# CPCISerial_connector.net
KiCad netlist of a schematic drawn in Altium Designer
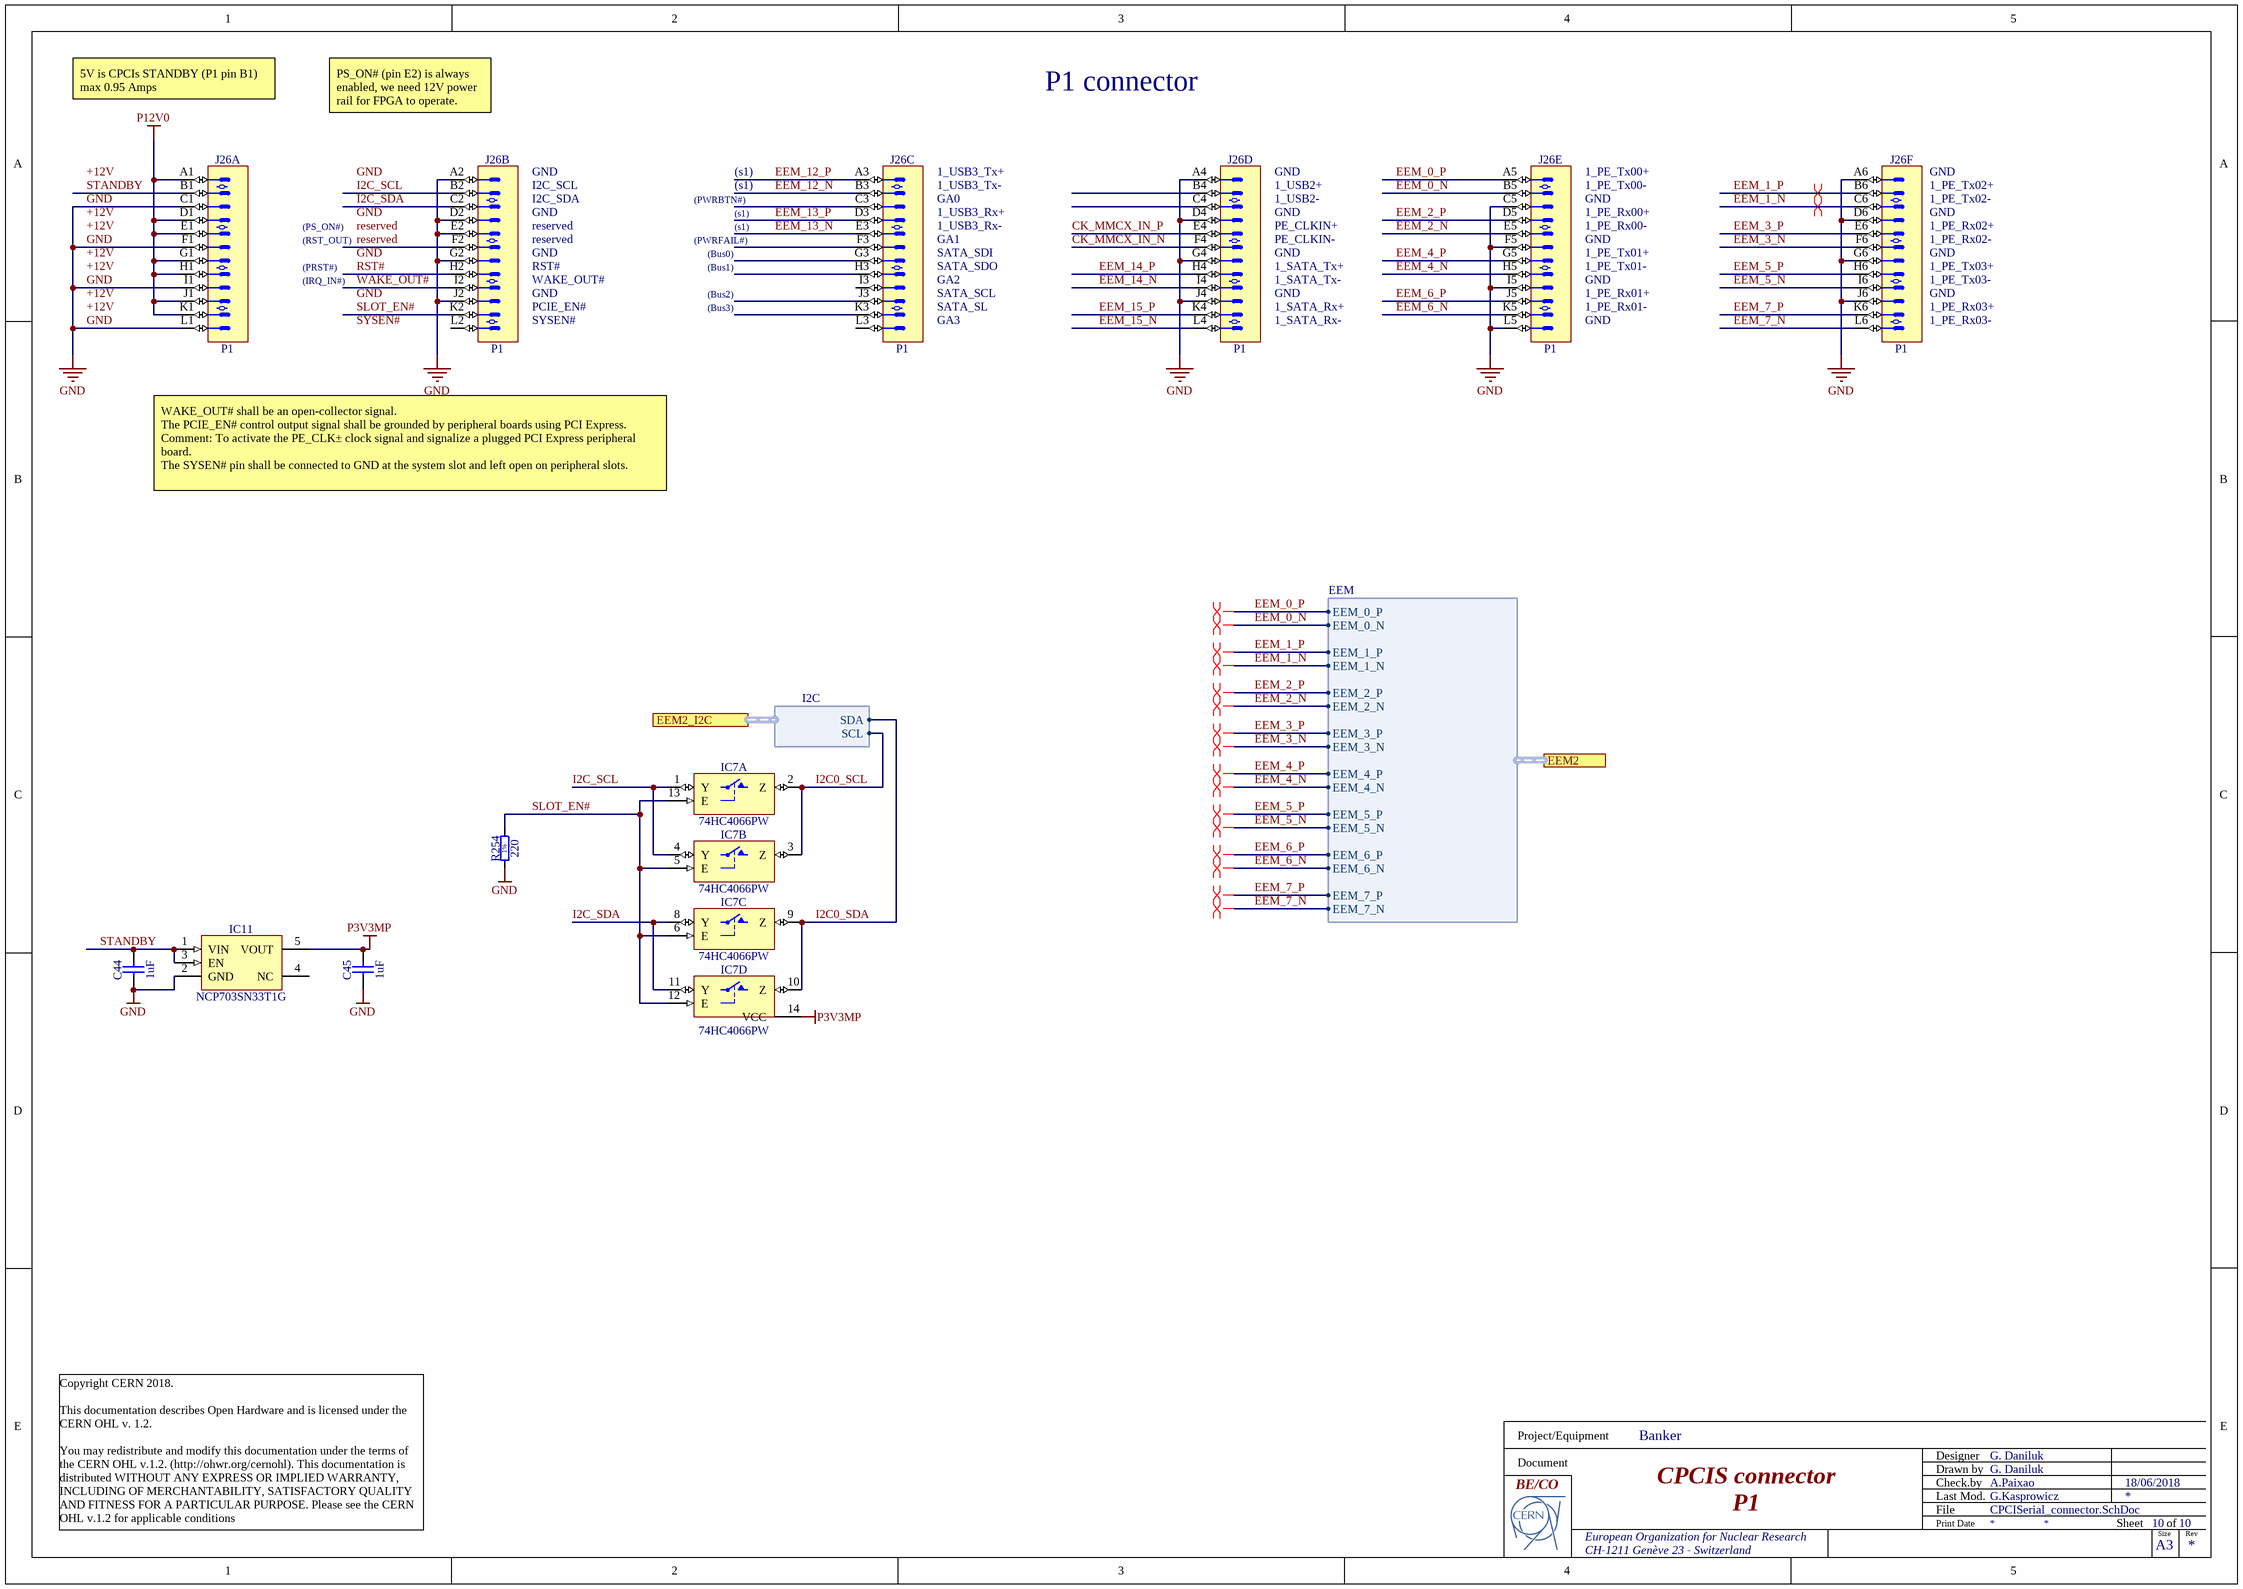
[diagram p0: CPCISerial_connector.SchDoc]

(export (version "E")
  (design (tool "Eeschema 10.0.6"))
  (components
    (comp (ref "C44")
      (value "1uF")
      (footprint "CAPC2012X140N")
      (description "Non-polarised capacitor")
      (fields
        (field (name "PART NUMBER") "CC0805_1UF_35V_20%_X7R")
        (field (name "VOLTAGE") "35V")
        (field (name "AUTHOR") "CERN DEM JLC")
      )
      (libsource (lib "Capacitors") (part "Capacitor - non polarized"))
    )
    (comp (ref "C45")
      (value "1uF")
      (footprint "CAPC2012X140N")
      (description "Non-polarised capacitor")
      (fields
        (field (name "PART NUMBER") "CC0805_1UF_35V_20%_X7R")
        (field (name "VOLTAGE") "35V")
        (field (name "AUTHOR") "CERN DEM JLC")
      )
      (libsource (lib "Capacitors") (part "Capacitor - non polarized"))
    )
    (comp (ref "IC7")
      (value "74HC4066PW")
      (footprint "SOP65P640X110-14N")
      (fields (field (name "MANUFACTURER") "NXP SEMICONDUCTORS") (field (name "AUTHOR") "CERN DEM JLC"))
      (libsource (lib "ICs And Semiconductors") (part "4066"))
    )
    (comp (ref "IC11")
      (value "NCP703SN33T1G")
      (footprint "SOT95P275X110-5N")
      (description "3.3V 300mA, Ultra-Low Quiescent Current, IQ 12uA, Ultra-Low Noise, LDO Voltage Regulator")
      (fields (field (name "MANUFACTURER") "ON SEMICONDUCTOR") (field (name "AUTHOR") "CERN DEM JLC"))
      (libsource (lib "ICs And Semiconductors") (part "NCP703SN"))
    )
    (comp (ref "J26")
      (value "P1")
      (footprint "AMPHENOL_10052825-101LF")
      (description "72 Contacts Header, 6 Columns, 4 Pairs per Column")
      (fields
        (field (name "PART NUMBER") "AMPHENOL_10052825-101LF")
        (field (name "MANUFACTURER") "AMPHENOL")
        (field (name "AUTHOR") "CERN DEM MR")
      )
      (libsource (lib "Connectors") (part "AMPHENOL_10052825-101LF"))
    )
    (comp (ref "R254")
      (value "220")
      (footprint "RESC1608X55N")
      (description "Resistor - 1%")
      (fields
        (field (name "PART NUMBER") "R0603_220R_1%_0.1W_100PPM")
        (field (name "POWER") "0.1W")
        (field (name "AUTHOR") "CERN DEM JLC")
      )
      (libsource (lib "Resistors") (part "Resistor - 1%"))
    )
  )
  (nets
    (net (code "4") (name "/CK_MMCX_IN_N") (class "Default")
      (node (ref "J26") (pin "F4") (pinfunction "F4_F4") (pintype "bidirectional"))
    )
    (net (code "5") (name "/CK_MMCX_IN_P") (class "Default")
      (node (ref "J26") (pin "E4") (pinfunction "E4_E4") (pintype "bidirectional"))
    )
    (net (code "6") (name "/EEM_0_N") (class "Default")
      (node (ref "J26") (pin "B5") (pinfunction "B5_B5") (pintype "bidirectional"))
    )
    (net (code "7") (name "/EEM_0_P") (class "Default")
      (node (ref "J26") (pin "A5") (pinfunction "A5_A5") (pintype "bidirectional"))
    )
    (net (code "8") (name "/EEM_1_N") (class "Default")
      (node (ref "J26") (pin "C6") (pinfunction "C6_C6") (pintype "bidirectional"))
    )
    (net (code "9") (name "/EEM_1_P") (class "Default")
      (node (ref "J26") (pin "B6") (pinfunction "B6_B6") (pintype "bidirectional"))
    )
    (net (code "10") (name "/EEM_2_N") (class "Default")
      (node (ref "J26") (pin "E5") (pinfunction "E5_E5") (pintype "bidirectional"))
    )
    (net (code "11") (name "/EEM_2_P") (class "Default")
      (node (ref "J26") (pin "D5") (pinfunction "D5_D5") (pintype "bidirectional"))
    )
    (net (code "12") (name "/EEM_3_N") (class "Default")
      (node (ref "J26") (pin "F6") (pinfunction "F6_F6") (pintype "bidirectional"))
    )
    (net (code "13") (name "/EEM_3_P") (class "Default")
      (node (ref "J26") (pin "E6") (pinfunction "E6_E6") (pintype "bidirectional"))
    )
    (net (code "14") (name "/EEM_4_N") (class "Default")
      (node (ref "J26") (pin "H5") (pinfunction "H5_H5") (pintype "bidirectional"))
    )
    (net (code "15") (name "/EEM_4_P") (class "Default")
      (node (ref "J26") (pin "G5") (pinfunction "G5_G5") (pintype "bidirectional"))
    )
    (net (code "16") (name "/EEM_5_N") (class "Default")
      (node (ref "J26") (pin "I6") (pinfunction "I6_I6") (pintype "bidirectional"))
    )
    (net (code "17") (name "/EEM_5_P") (class "Default")
      (node (ref "J26") (pin "H6") (pinfunction "H6_H6") (pintype "bidirectional"))
    )
    (net (code "18") (name "/EEM_6_N") (class "Default")
      (node (ref "J26") (pin "K5") (pinfunction "K5_K5") (pintype "bidirectional"))
    )
    (net (code "19") (name "/EEM_6_P") (class "Default")
      (node (ref "J26") (pin "J5") (pinfunction "J5_J5") (pintype "bidirectional"))
    )
    (net (code "20") (name "/EEM_7_N") (class "Default")
      (node (ref "J26") (pin "L6") (pinfunction "L6_L6") (pintype "bidirectional"))
    )
    (net (code "21") (name "/EEM_7_P") (class "Default")
      (node (ref "J26") (pin "K6") (pinfunction "K6_K6") (pintype "bidirectional"))
    )
    (net (code "22") (name "/EEM_12_N") (class "Default")
      (node (ref "J26") (pin "B3") (pinfunction "B3_B3") (pintype "bidirectional"))
    )
    (net (code "23") (name "/EEM_12_P") (class "Default")
      (node (ref "J26") (pin "A3") (pinfunction "A3_A3") (pintype "bidirectional"))
    )
    (net (code "24") (name "/EEM_13_N") (class "Default")
      (node (ref "J26") (pin "E3") (pinfunction "E3_E3") (pintype "bidirectional"))
    )
    (net (code "25") (name "/EEM_13_P") (class "Default")
      (node (ref "J26") (pin "D3") (pinfunction "D3_D3") (pintype "bidirectional"))
    )
    (net (code "26") (name "/EEM_14_N") (class "Default")
      (node (ref "J26") (pin "I4") (pinfunction "I4_I4") (pintype "bidirectional"))
    )
    (net (code "27") (name "/EEM_14_P") (class "Default")
      (node (ref "J26") (pin "H4") (pinfunction "H4_H4") (pintype "bidirectional"))
    )
    (net (code "28") (name "/EEM_15_N") (class "Default")
      (node (ref "J26") (pin "L4") (pinfunction "L4_L4") (pintype "bidirectional"))
    )
    (net (code "29") (name "/EEM_15_P") (class "Default")
      (node (ref "J26") (pin "K4") (pinfunction "K4_K4") (pintype "bidirectional"))
    )
    (net (code "30") (name "/I2C0_SCL") (class "Default")
      (node (ref "IC7") (pin "2") (pinfunction "Z_2") (pintype "bidirectional"))
      (node (ref "IC7") (pin "3") (pinfunction "Z_3") (pintype "bidirectional"))
    )
    (net (code "31") (name "/I2C0_SDA") (class "Default")
      (node (ref "IC7") (pin "10") (pinfunction "Z_10") (pintype "bidirectional"))
      (node (ref "IC7") (pin "9") (pinfunction "Z_9") (pintype "bidirectional"))
    )
    (net (code "32") (name "/I2C_SCL") (class "Default")
      (node (ref "IC7") (pin "1") (pinfunction "Y_1") (pintype "bidirectional"))
      (node (ref "IC7") (pin "4") (pinfunction "Y_4") (pintype "bidirectional"))
      (node (ref "J26") (pin "B2") (pinfunction "B2_B2") (pintype "bidirectional"))
    )
    (net (code "33") (name "/I2C_SDA") (class "Default")
      (node (ref "IC7") (pin "11") (pinfunction "Y_11") (pintype "bidirectional"))
      (node (ref "IC7") (pin "8") (pinfunction "Y_8") (pintype "bidirectional"))
      (node (ref "J26") (pin "C2") (pinfunction "C2_C2") (pintype "bidirectional"))
    )
    (net (code "34") (name "/RST#") (class "Default")
      (node (ref "J26") (pin "H2") (pinfunction "H2_H2") (pintype "bidirectional"))
    )
    (net (code "35") (name "/SLOT_EN#") (class "Default")
      (node (ref "IC7") (pin "12") (pinfunction "E_12") (pintype "input"))
      (node (ref "IC7") (pin "13") (pinfunction "E_13") (pintype "input"))
      (node (ref "IC7") (pin "5") (pinfunction "E_5") (pintype "input"))
      (node (ref "IC7") (pin "6") (pinfunction "E_6") (pintype "input"))
      (node (ref "J26") (pin "K2") (pinfunction "K2_K2") (pintype "bidirectional"))
      (node (ref "R254") (pin "2") (pinfunction "2_2") (pintype "passive"))
    )
    (net (code "36") (name "/STANDBY") (class "Default")
      (node (ref "C44") (pin "2") (pinfunction "2_2") (pintype "passive"))
      (node (ref "IC11") (pin "1") (pinfunction "VIN_1") (pintype "input"))
      (node (ref "IC11") (pin "3") (pinfunction "EN_3") (pintype "input"))
      (node (ref "J26") (pin "B1") (pinfunction "B1_B1") (pintype "bidirectional"))
    )
    (net (code "38") (name "/WAKE_OUT#") (class "Default")
      (node (ref "J26") (pin "I2") (pinfunction "I2_I2") (pintype "bidirectional"))
    )
    (net (code "39") (name "/reserved") (class "Default")
      (node (ref "J26") (pin "F2") (pinfunction "F2_F2") (pintype "bidirectional"))
    )
    (net (code "42") (name "GND") (class "Default")
      (node (ref "C44") (pin "1") (pinfunction "1_1") (pintype "passive"))
      (node (ref "C45") (pin "1") (pinfunction "1_1") (pintype "passive"))
      (node (ref "IC11") (pin "2") (pinfunction "GND_2") (pintype "power_in"))
      (node (ref "IC7") (pin "7") (pinfunction "GND_7") (pintype "power_in"))
      (node (ref "J26") (pin "A2") (pinfunction "A2_A2") (pintype "bidirectional"))
      (node (ref "J26") (pin "A4") (pinfunction "A4_A4") (pintype "bidirectional"))
      (node (ref "J26") (pin "A6") (pinfunction "A6_A6") (pintype "bidirectional"))
      (node (ref "J26") (pin "C1") (pinfunction "C1_C1") (pintype "bidirectional"))
      (node (ref "J26") (pin "C5") (pinfunction "C5_C5") (pintype "bidirectional"))
      (node (ref "J26") (pin "D2") (pinfunction "D2_D2") (pintype "bidirectional"))
      (node (ref "J26") (pin "D4") (pinfunction "D4_D4") (pintype "bidirectional"))
      (node (ref "J26") (pin "D6") (pinfunction "D6_D6") (pintype "bidirectional"))
      (node (ref "J26") (pin "E2") (pinfunction "E2_E2") (pintype "bidirectional"))
      (node (ref "J26") (pin "F1") (pinfunction "F1_F1") (pintype "bidirectional"))
      (node (ref "J26") (pin "F5") (pinfunction "F5_F5") (pintype "bidirectional"))
      (node (ref "J26") (pin "G2") (pinfunction "G2_G2") (pintype "bidirectional"))
      (node (ref "J26") (pin "G4") (pinfunction "G4_G4") (pintype "bidirectional"))
      (node (ref "J26") (pin "G6") (pinfunction "G6_G6") (pintype "bidirectional"))
      (node (ref "J26") (pin "I1") (pinfunction "I1_I1") (pintype "bidirectional"))
      (node (ref "J26") (pin "I5") (pinfunction "I5_I5") (pintype "bidirectional"))
      (node (ref "J26") (pin "J2") (pinfunction "J2_J2") (pintype "bidirectional"))
      (node (ref "J26") (pin "J4") (pinfunction "J4_J4") (pintype "bidirectional"))
      (node (ref "J26") (pin "J6") (pinfunction "J6_J6") (pintype "bidirectional"))
      (node (ref "J26") (pin "L1") (pinfunction "L1_L1") (pintype "bidirectional"))
      (node (ref "J26") (pin "L5") (pinfunction "L5_L5") (pintype "bidirectional"))
      (node (ref "R254") (pin "1") (pinfunction "1_1") (pintype "passive"))
    )
    (net (code "43") (name "P3V3MP") (class "Default")
      (node (ref "C45") (pin "2") (pinfunction "2_2") (pintype "passive"))
      (node (ref "IC11") (pin "5") (pinfunction "VOUT_5") (pintype "power_in"))
      (node (ref "IC7") (pin "14") (pinfunction "VCC_14") (pintype "power_in"))
    )
    (net (code "44") (name "P12V0") (class "Default")
      (node (ref "J26") (pin "A1") (pinfunction "A1_A1") (pintype "bidirectional"))
      (node (ref "J26") (pin "D1") (pinfunction "D1_D1") (pintype "bidirectional"))
      (node (ref "J26") (pin "E1") (pinfunction "E1_E1") (pintype "bidirectional"))
      (node (ref "J26") (pin "G1") (pinfunction "G1_G1") (pintype "bidirectional"))
      (node (ref "J26") (pin "H1") (pinfunction "H1_H1") (pintype "bidirectional"))
      (node (ref "J26") (pin "J1") (pinfunction "J1_J1") (pintype "bidirectional"))
      (node (ref "J26") (pin "K1") (pinfunction "K1_K1") (pintype "bidirectional"))
    )
    (net (code "45") (name "unconnected-(IC11-NC-Pad4)") (class "Default")
      (node (ref "IC11") (pin "4") (pinfunction "NC_4") (pintype "passive"))
    )
    (net (code "46") (name "unconnected-(J26-PadB4)") (class "Default")
      (node (ref "J26") (pin "B4") (pinfunction "B4_B4") (pintype "bidirectional"))
    )
    (net (code "47") (name "unconnected-(J26-PadC3)") (class "Default")
      (node (ref "J26") (pin "C3") (pinfunction "C3_C3") (pintype "bidirectional"))
    )
    (net (code "48") (name "unconnected-(J26-PadC4)") (class "Default")
      (node (ref "J26") (pin "C4") (pinfunction "C4_C4") (pintype "bidirectional"))
    )
    (net (code "49") (name "unconnected-(J26-PadF3)") (class "Default")
      (node (ref "J26") (pin "F3") (pinfunction "F3_F3") (pintype "bidirectional"))
    )
    (net (code "50") (name "unconnected-(J26-PadG3)") (class "Default")
      (node (ref "J26") (pin "G3") (pinfunction "G3_G3") (pintype "bidirectional"))
    )
    (net (code "51") (name "unconnected-(J26-PadH3)") (class "Default")
      (node (ref "J26") (pin "H3") (pinfunction "H3_H3") (pintype "bidirectional"))
    )
    (net (code "52") (name "unconnected-(J26-PadI3)") (class "Default")
      (node (ref "J26") (pin "I3") (pinfunction "I3_I3") (pintype "bidirectional"))
    )
    (net (code "53") (name "unconnected-(J26-PadJ3)") (class "Default")
      (node (ref "J26") (pin "J3") (pinfunction "J3_J3") (pintype "bidirectional"))
    )
    (net (code "54") (name "unconnected-(J26-PadK3)") (class "Default")
      (node (ref "J26") (pin "K3") (pinfunction "K3_K3") (pintype "bidirectional"))
    )
    (net (code "55") (name "unconnected-(J26-PadL2)") (class "Default")
      (node (ref "J26") (pin "L2") (pinfunction "L2_L2") (pintype "bidirectional"))
    )
    (net (code "56") (name "unconnected-(J26-PadL3)") (class "Default")
      (node (ref "J26") (pin "L3") (pinfunction "L3_L3") (pintype "bidirectional"))
    )
  )
)
